# Sch1_TP2_EJ3.net
KiCad netlist of a schematic drawn in Altium Designer
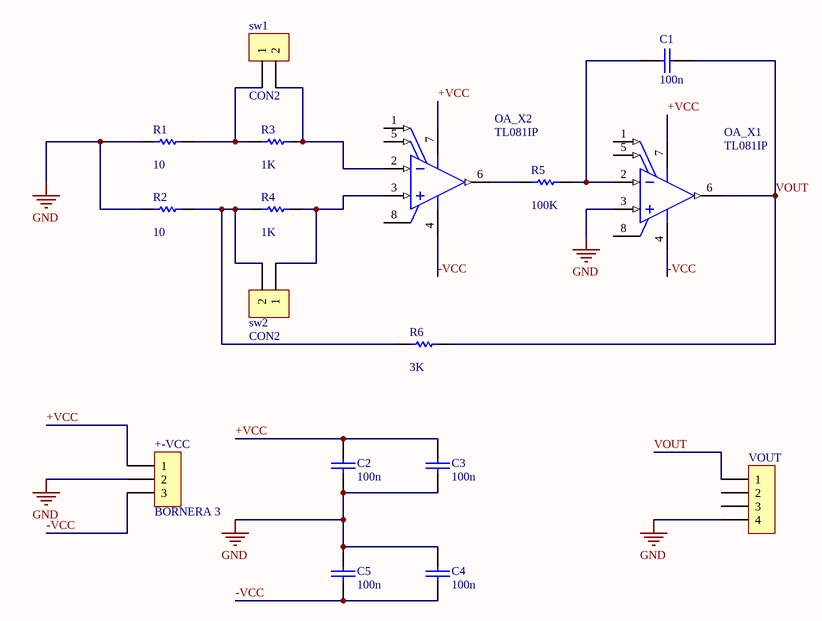
[diagram p0: Sch1_TP2_EJ3.SchDoc]

(export (version "E")
  (design (tool "Eeschema 10.0.6"))
  (components
    (comp (ref "+-VCC")
      (value "BORNERA 3")
      (footprint "BORNERA3")
      (libsource (lib "LIBEBAL") (part "BORNERA 3"))
    )
    (comp (ref "C1") (value "100n") (footprint "CAP100") (libsource (lib "LIB PIO IX") (part "CAP")))
    (comp (ref "C2") (value "100n") (footprint "CAP100") (libsource (lib "LIBEBAL") (part "CAP")))
    (comp (ref "C3") (value "100n") (footprint "CAP100") (libsource (lib "LIBEBAL") (part "CAP")))
    (comp (ref "C4") (value "100n") (footprint "CAP100") (libsource (lib "LIBEBAL") (part "CAP")))
    (comp (ref "C5") (value "100n") (footprint "CAP100") (libsource (lib "LIBEBAL") (part "CAP")))
    (comp (ref "OA_X1")
      (value "TL081IP")
      (footprint "TI-P8")
      (description "JFET-Input Operational Amplifier, 7 to 36 V, -40 to 85 degC, 8-pin DIP (P8), Pb-Free (RoHS)")
      (fields (field (name "MANUFACTURER") "Texas Instruments"))
      (libsource (lib "TI Amplifiers and Linear Operational Amplifier General Purpose") (part "TL081IP"))
    )
    (comp (ref "OA_X2")
      (value "TL081IP")
      (footprint "TI-P8")
      (description "JFET-Input Operational Amplifier, 7 to 36 V, -40 to 85 degC, 8-pin DIP (P8), Pb-Free (RoHS)")
      (fields (field (name "MANUFACTURER") "Texas Instruments"))
      (libsource (lib "TI Amplifiers and Linear Operational Amplifier General Purpose") (part "TL081IP"))
    )
    (comp (ref "R1")
      (value "10")
      (footprint "AXIAL-0.3")
      (description "Resistor")
      (fields (field (name "PUBLISHER") "Altium Limited"))
      (libsource (lib "Miscellaneous Devices") (part "Res1"))
    )
    (comp (ref "R2")
      (value "10")
      (footprint "AXIAL-0.3")
      (description "Resistor")
      (fields (field (name "PUBLISHER") "Altium Limited"))
      (libsource (lib "Miscellaneous Devices") (part "Res1"))
    )
    (comp (ref "R3")
      (value "1K")
      (footprint "AXIAL-0.3")
      (description "Resistor")
      (fields (field (name "PUBLISHER") "Altium Limited"))
      (libsource (lib "Miscellaneous Devices") (part "Res1"))
    )
    (comp (ref "R4")
      (value "1K")
      (footprint "AXIAL-0.3")
      (description "Resistor")
      (fields (field (name "PUBLISHER") "Altium Limited"))
      (libsource (lib "Miscellaneous Devices") (part "Res1"))
    )
    (comp (ref "R5")
      (value "100K")
      (footprint "AXIAL-0.3")
      (description "Resistor")
      (fields (field (name "PUBLISHER") "Altium Limited"))
      (libsource (lib "Miscellaneous Devices") (part "Res1"))
    )
    (comp (ref "R6")
      (value "3K")
      (footprint "AXIAL-0.3")
      (description "Resistor")
      (fields (field (name "PUBLISHER") "Altium Limited"))
      (libsource (lib "Miscellaneous Devices") (part "Res1"))
    )
    (comp (ref "sw1") (value "CON2") (footprint "SIP2") (libsource (lib "") (part "CON2_1")))
    (comp (ref "sw2") (value "CON2") (footprint "SIP2") (libsource (lib "LIBEBAL") (part "CON2")))
    (comp (ref "VOUT") (value "~") (footprint "SIP4") (libsource (lib "LIBEBAL") (part "CON4")))
  )
  (nets
    (net (code "1") (name "/+VCC") (class "Default")
      (node (ref "+-VCC") (pin "1") (pinfunction "1_1") (pintype "passive"))
      (node (ref "C2") (pin "1") (pinfunction "1_1") (pintype "passive"))
      (node (ref "C3") (pin "1") (pinfunction "1_1") (pintype "passive"))
      (node (ref "OA_X1") (pin "7") (pinfunction "VCC+_7") (pintype "power_in"))
      (node (ref "OA_X2") (pin "7") (pinfunction "VCC+_7") (pintype "power_in"))
    )
    (net (code "2") (name "/-VCC") (class "Default")
      (node (ref "+-VCC") (pin "3") (pinfunction "3_3") (pintype "passive"))
      (node (ref "C4") (pin "2") (pinfunction "2_2") (pintype "passive"))
      (node (ref "C5") (pin "2") (pinfunction "2_2") (pintype "passive"))
      (node (ref "OA_X1") (pin "4") (pinfunction "VCC-_4") (pintype "power_in"))
      (node (ref "OA_X2") (pin "4") (pinfunction "VCC-_4") (pintype "power_in"))
    )
    (net (code "3") (name "/VOUT") (class "Default")
      (node (ref "C1") (pin "2") (pinfunction "2_2") (pintype "passive"))
      (node (ref "OA_X1") (pin "6") (pinfunction "OUT_6") (pintype "output"))
      (node (ref "R6") (pin "2") (pinfunction "2_2") (pintype "passive"))
      (node (ref "VOUT") (pin "1") (pinfunction "1_1") (pintype "passive"))
    )
    (net (code "4") (name "GND") (class "Default")
      (node (ref "+-VCC") (pin "2") (pinfunction "2_2") (pintype "passive"))
      (node (ref "C2") (pin "2") (pinfunction "2_2") (pintype "passive"))
      (node (ref "C3") (pin "2") (pinfunction "2_2") (pintype "passive"))
      (node (ref "C4") (pin "1") (pinfunction "1_1") (pintype "passive"))
      (node (ref "C5") (pin "1") (pinfunction "1_1") (pintype "passive"))
      (node (ref "OA_X1") (pin "3") (pinfunction "IN+_3") (pintype "input"))
      (node (ref "R1") (pin "1") (pinfunction "1_1") (pintype "passive"))
      (node (ref "R2") (pin "1") (pinfunction "1_1") (pintype "passive"))
      (node (ref "VOUT") (pin "4") (pinfunction "4_4") (pintype "passive"))
    )
    (net (code "5") (name "Net-(OA_X1-IN-)") (class "Default")
      (node (ref "C1") (pin "1") (pinfunction "1_1") (pintype "passive"))
      (node (ref "OA_X1") (pin "2") (pinfunction "IN-_2") (pintype "input"))
      (node (ref "R5") (pin "2") (pinfunction "2_2") (pintype "passive"))
    )
    (net (code "6") (name "Net-(OA_X2-IN+)") (class "Default")
      (node (ref "OA_X2") (pin "3") (pinfunction "IN+_3") (pintype "input"))
      (node (ref "R4") (pin "2") (pinfunction "2_2") (pintype "passive"))
      (node (ref "sw2") (pin "1") (pinfunction "1_1") (pintype "passive"))
    )
    (net (code "7") (name "Net-(OA_X2-IN-)") (class "Default")
      (node (ref "OA_X2") (pin "2") (pinfunction "IN-_2") (pintype "input"))
      (node (ref "R3") (pin "2") (pinfunction "2_2") (pintype "passive"))
      (node (ref "sw1") (pin "2") (pinfunction "2_2") (pintype "passive"))
    )
    (net (code "8") (name "Net-(OA_X2-OUT)") (class "Default")
      (node (ref "OA_X2") (pin "6") (pinfunction "OUT_6") (pintype "output"))
      (node (ref "R5") (pin "1") (pinfunction "1_1") (pintype "passive"))
    )
    (net (code "9") (name "Net-(R1-Pad2)") (class "Default")
      (node (ref "R1") (pin "2") (pinfunction "2_2") (pintype "passive"))
      (node (ref "R3") (pin "1") (pinfunction "1_1") (pintype "passive"))
      (node (ref "sw1") (pin "1") (pinfunction "1_1") (pintype "passive"))
    )
    (net (code "10") (name "Net-(R2-Pad2)") (class "Default")
      (node (ref "R2") (pin "2") (pinfunction "2_2") (pintype "passive"))
      (node (ref "R4") (pin "1") (pinfunction "1_1") (pintype "passive"))
      (node (ref "R6") (pin "1") (pinfunction "1_1") (pintype "passive"))
      (node (ref "sw2") (pin "2") (pinfunction "2_2") (pintype "passive"))
    )
    (net (code "11") (name "unconnected-(OA_X1-NC-Pad8)") (class "Default")
      (node (ref "OA_X1") (pin "8") (pinfunction "NC_8") (pintype "passive"))
    )
    (net (code "12") (name "unconnected-(OA_X1-OFFSET_N1-Pad1)") (class "Default")
      (node (ref "OA_X1") (pin "1") (pinfunction "OFFSET_N1_1") (pintype "input"))
    )
    (net (code "13") (name "unconnected-(OA_X1-OFFSET_N2-Pad5)") (class "Default")
      (node (ref "OA_X1") (pin "5") (pinfunction "OFFSET_N2_5") (pintype "input"))
    )
    (net (code "14") (name "unconnected-(OA_X2-NC-Pad8)") (class "Default")
      (node (ref "OA_X2") (pin "8") (pinfunction "NC_8") (pintype "passive"))
    )
    (net (code "15") (name "unconnected-(OA_X2-OFFSET_N1-Pad1)") (class "Default")
      (node (ref "OA_X2") (pin "1") (pinfunction "OFFSET_N1_1") (pintype "input"))
    )
    (net (code "16") (name "unconnected-(OA_X2-OFFSET_N2-Pad5)") (class "Default")
      (node (ref "OA_X2") (pin "5") (pinfunction "OFFSET_N2_5") (pintype "input"))
    )
    (net (code "17") (name "unconnected-(VOUT-Pad2)") (class "Default")
      (node (ref "VOUT") (pin "2") (pinfunction "2_2") (pintype "passive"))
    )
    (net (code "18") (name "unconnected-(VOUT-Pad3)") (class "Default")
      (node (ref "VOUT") (pin "3") (pinfunction "3_3") (pintype "passive"))
    )
  )
)
